# Communication_connectors_headers.net
KiCad netlist of a schematic drawn in Altium Designer
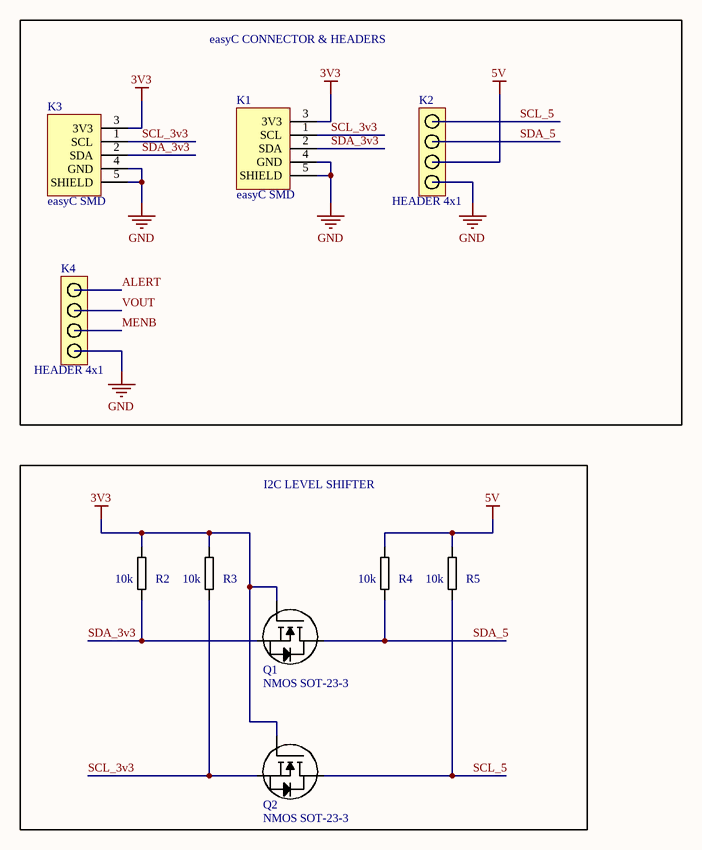
[diagram p0: Communication, connectors & headers.SchDoc]

(export (version "E")
  (design (tool "Eeschema 10.0.6"))
  (components
    (comp (ref "K1")
      (value "easyC SMD")
      (footprint "EasyC connector")
      (libsource (lib "TAVU Altium library") (part "easyC SMD"))
    )
    (comp (ref "K2")
      (value "HEADER 4x1")
      (footprint "HEADER MALE 4x1")
      (libsource (lib "TAVU Altium library") (part "HEADER 4x1"))
    )
    (comp (ref "K3")
      (value "easyC SMD")
      (footprint "EasyC connector")
      (libsource (lib "TAVU Altium library") (part "easyC SMD"))
    )
    (comp (ref "K4")
      (value "HEADER 4x1")
      (footprint "HEADER MALE 4x1")
      (libsource (lib "TAVU Altium library") (part "HEADER 4x1"))
    )
    (comp (ref "Q1")
      (value "NMOS SOT-23-3")
      (footprint "SOT-23-3")
      (libsource (lib "TAVU Altium library") (part "NMOS SOT-23-3"))
    )
    (comp (ref "Q2")
      (value "NMOS SOT-23-3")
      (footprint "SOT-23-3")
      (libsource (lib "TAVU Altium library") (part "NMOS SOT-23-3"))
    )
    (comp (ref "R2") (value "10k") (footprint "0603R") (libsource (lib "TAVU Altium library") (part "0603R")))
    (comp (ref "R3") (value "10k") (footprint "0603R") (libsource (lib "TAVU Altium library") (part "0603R")))
    (comp (ref "R4") (value "10k") (footprint "0603R") (libsource (lib "TAVU Altium library") (part "0603R")))
    (comp (ref "R5") (value "10k") (footprint "0603R") (libsource (lib "TAVU Altium library") (part "0603R")))
  )
  (nets
    (net (code "1") (name "/ALERT") (class "Default")
      (node (ref "K4") (pin "1") (pinfunction "1_1") (pintype "passive"))
    )
    (net (code "2") (name "/MENB") (class "Default")
      (node (ref "K4") (pin "3") (pinfunction "3_3") (pintype "passive"))
    )
    (net (code "3") (name "/SCL_3v3") (class "Default")
      (node (ref "K1") (pin "1") (pinfunction "SCL_1") (pintype "passive"))
      (node (ref "K3") (pin "1") (pinfunction "SCL_1") (pintype "passive"))
      (node (ref "Q2") (pin "2") (pinfunction "S_2") (pintype "passive"))
      (node (ref "R3") (pin "1") (pinfunction "1_1") (pintype "passive"))
    )
    (net (code "4") (name "/SCL_5") (class "Default")
      (node (ref "K2") (pin "1") (pinfunction "1_1") (pintype "passive"))
      (node (ref "Q2") (pin "3") (pinfunction "D_3") (pintype "passive"))
      (node (ref "R5") (pin "1") (pinfunction "1_1") (pintype "passive"))
    )
    (net (code "5") (name "/SDA_3v3") (class "Default")
      (node (ref "K1") (pin "2") (pinfunction "SDA_2") (pintype "passive"))
      (node (ref "K3") (pin "2") (pinfunction "SDA_2") (pintype "passive"))
      (node (ref "Q1") (pin "2") (pinfunction "S_2") (pintype "passive"))
      (node (ref "R2") (pin "1") (pinfunction "1_1") (pintype "passive"))
    )
    (net (code "6") (name "/SDA_5") (class "Default")
      (node (ref "K2") (pin "2") (pinfunction "2_2") (pintype "passive"))
      (node (ref "Q1") (pin "3") (pinfunction "D_3") (pintype "passive"))
      (node (ref "R4") (pin "1") (pinfunction "1_1") (pintype "passive"))
    )
    (net (code "7") (name "/VOUT") (class "Default")
      (node (ref "K4") (pin "2") (pinfunction "2_2") (pintype "passive"))
    )
    (net (code "8") (name "3V3") (class "Default")
      (node (ref "K1") (pin "3") (pinfunction "3V3_3") (pintype "passive"))
      (node (ref "K3") (pin "3") (pinfunction "3V3_3") (pintype "passive"))
      (node (ref "Q1") (pin "1") (pinfunction "G_1") (pintype "passive"))
      (node (ref "Q2") (pin "1") (pinfunction "G_1") (pintype "passive"))
      (node (ref "R2") (pin "2") (pinfunction "2_2") (pintype "passive"))
      (node (ref "R3") (pin "2") (pinfunction "2_2") (pintype "passive"))
    )
    (net (code "9") (name "5V") (class "Default")
      (node (ref "K2") (pin "3") (pinfunction "3_3") (pintype "passive"))
      (node (ref "R4") (pin "2") (pinfunction "2_2") (pintype "passive"))
      (node (ref "R5") (pin "2") (pinfunction "2_2") (pintype "passive"))
    )
    (net (code "10") (name "GND") (class "Default")
      (node (ref "K1") (pin "4") (pinfunction "GND_4") (pintype "passive"))
      (node (ref "K1") (pin "5") (pinfunction "SHIELD_5") (pintype "passive"))
      (node (ref "K2") (pin "4") (pinfunction "4_4") (pintype "passive"))
      (node (ref "K3") (pin "4") (pinfunction "GND_4") (pintype "passive"))
      (node (ref "K3") (pin "5") (pinfunction "SHIELD_5") (pintype "passive"))
      (node (ref "K4") (pin "4") (pinfunction "4_4") (pintype "passive"))
    )
  )
)
